# bristol_longshot.net
KiCad netlist of a schematic drawn in EAGLE
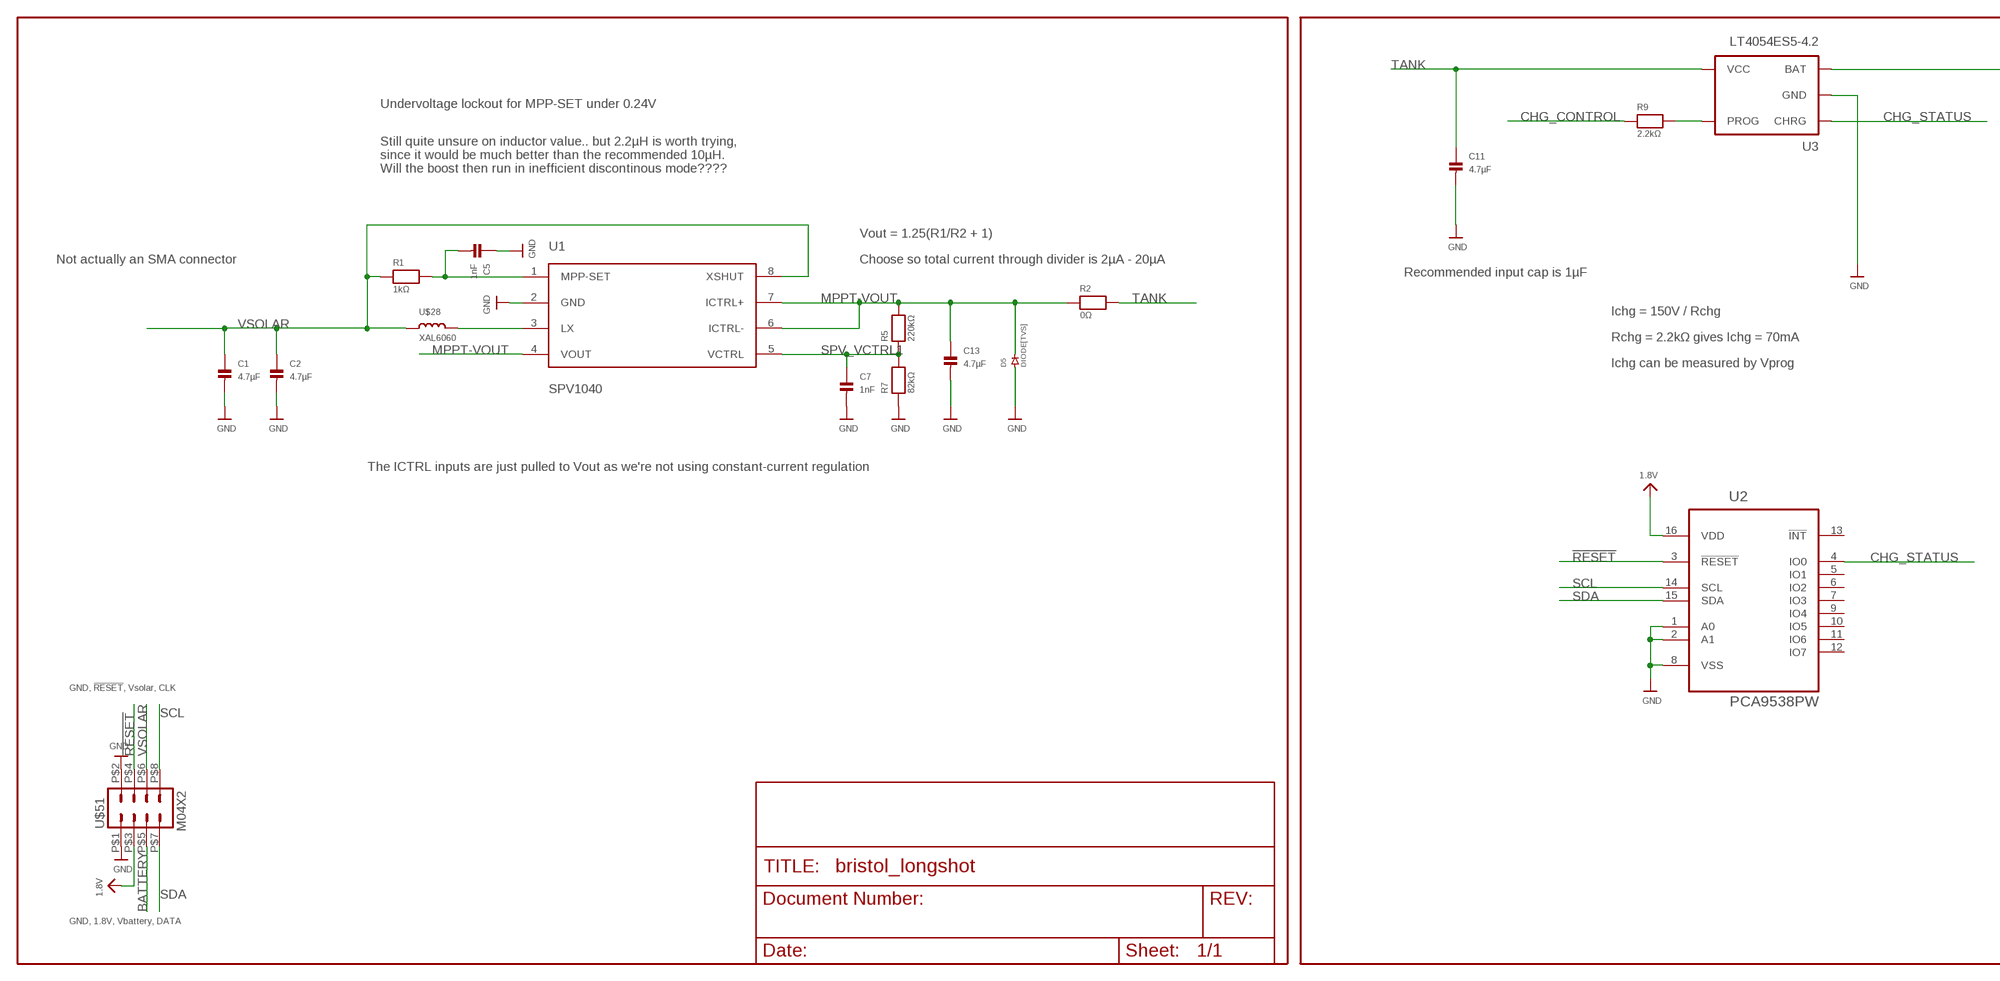
[diagram p0: schematic, sheet 1, part 1 of 2]
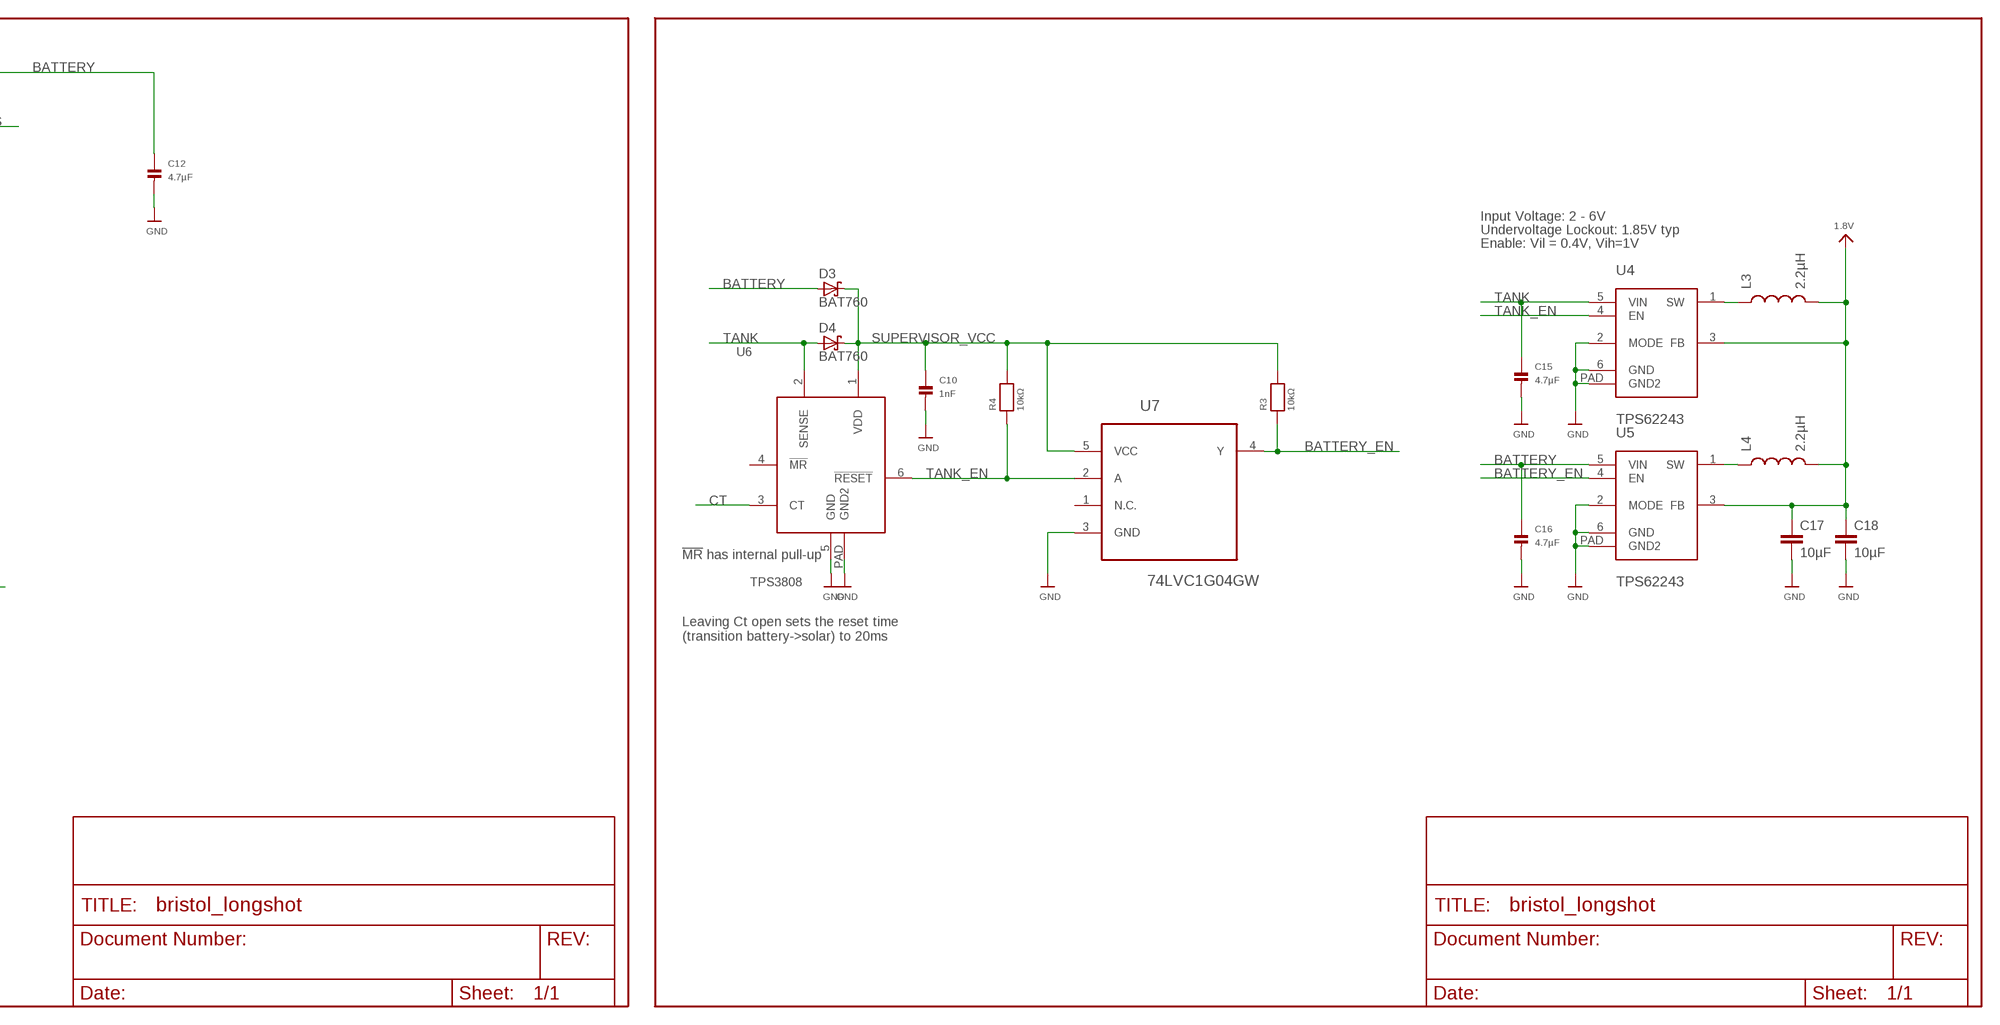
[diagram p1: schematic, sheet 1, part 2 of 2]

(export (version "E")
  (design (tool "Eeschema 10.0.6"))
  (components
    (comp (ref "C1")
      (value "4.7µF")
      (footprint "eagle-import:_0402")
      (libsource (lib "eagle-import") (part "CAP_CERAMIC_0402"))
    )
    (comp (ref "C2")
      (value "4.7µF")
      (footprint "eagle-import:_0402")
      (libsource (lib "eagle-import") (part "CAP_CERAMIC_0402"))
    )
    (comp (ref "C5")
      (value "1nF")
      (footprint "eagle-import:_0402")
      (libsource (lib "eagle-import") (part "CAP_CERAMIC_0402"))
    )
    (comp (ref "C7")
      (value "1nF")
      (footprint "eagle-import:_0402")
      (libsource (lib "eagle-import") (part "CAP_CERAMIC_0402"))
    )
    (comp (ref "C10")
      (value "1nF")
      (footprint "eagle-import:_0402")
      (libsource (lib "eagle-import") (part "CAP_CERAMIC_0402"))
    )
    (comp (ref "C11")
      (value "4.7µF")
      (footprint "eagle-import:_0402")
      (libsource (lib "eagle-import") (part "CAP_CERAMIC_0402"))
    )
    (comp (ref "C12")
      (value "4.7µF")
      (footprint "eagle-import:_0402")
      (libsource (lib "eagle-import") (part "CAP_CERAMIC_0402"))
    )
    (comp (ref "C13")
      (value "4.7µF")
      (footprint "eagle-import:_0402")
      (libsource (lib "eagle-import") (part "CAP_CERAMIC_0402"))
    )
    (comp (ref "C15")
      (value "4.7µF")
      (footprint "eagle-import:_0402")
      (libsource (lib "eagle-import") (part "CAP_CERAMIC_0402"))
    )
    (comp (ref "C16")
      (value "4.7µF")
      (footprint "eagle-import:_0402")
      (libsource (lib "eagle-import") (part "CAP_CERAMIC_0402"))
    )
    (comp (ref "C17")
      (value "10µF")
      (footprint "eagle-import:C0603K")
      (libsource (lib "eagle-import") (part "C-EUC0603K"))
    )
    (comp (ref "C18")
      (value "10µF")
      (footprint "eagle-import:C0603K")
      (libsource (lib "eagle-import") (part "C-EUC0603K"))
    )
    (comp (ref "D3")
      (value "BAT760")
      (footprint "eagle-import:SOD323")
      (libsource (lib "eagle-import") (part "BAT760"))
    )
    (comp (ref "D4")
      (value "BAT760")
      (footprint "eagle-import:SOD323")
      (libsource (lib "eagle-import") (part "BAT760"))
    )
    (comp (ref "D5")
      (value "DIODE[TVS]")
      (footprint "eagle-import:SOD123W")
      (libsource (lib "eagle-import") (part "DIODE[TVS]"))
    )
    (comp (ref "L3")
      (value "2.2µH")
      (footprint "eagle-import:1007")
      (libsource (lib "eagle-import") (part "INDUCTOR1007"))
    )
    (comp (ref "L4")
      (value "2.2µH")
      (footprint "eagle-import:1007")
      (libsource (lib "eagle-import") (part "INDUCTOR1007"))
    )
    (comp (ref "R1")
      (value "1kΩ")
      (footprint "eagle-import:_0402")
      (libsource (lib "eagle-import") (part "RESISTOR_0402"))
    )
    (comp (ref "R2")
      (value "0Ω")
      (footprint "eagle-import:_0402")
      (libsource (lib "eagle-import") (part "RESISTOR_0402"))
    )
    (comp (ref "R3")
      (value "10kΩ")
      (footprint "eagle-import:_0402")
      (libsource (lib "eagle-import") (part "RESISTOR_0402"))
    )
    (comp (ref "R4")
      (value "10kΩ")
      (footprint "eagle-import:_0402")
      (libsource (lib "eagle-import") (part "RESISTOR_0402"))
    )
    (comp (ref "R5")
      (value "220kΩ")
      (footprint "eagle-import:_0402")
      (libsource (lib "eagle-import") (part "RESISTOR_0402"))
    )
    (comp (ref "R7")
      (value "82kΩ")
      (footprint "eagle-import:_0402")
      (libsource (lib "eagle-import") (part "RESISTOR_0402"))
    )
    (comp (ref "R9")
      (value "2.2kΩ")
      (footprint "eagle-import:_0402")
      (libsource (lib "eagle-import") (part "RESISTOR_0402"))
    )
    (comp (ref "U$28")
      (value "XAL6060")
      (footprint "eagle-import:XAL60")
      (libsource (lib "eagle-import") (part "XAL6060"))
    )
    (comp (ref "U$51")
      (value "M04X2")
      (footprint "eagle-import:M04X2")
      (libsource (lib "eagle-import") (part "M04X2"))
    )
    (comp (ref "U1")
      (value "SPV1040")
      (footprint "eagle-import:TSSOP8")
      (libsource (lib "eagle-import") (part "SPV1040"))
    )
    (comp (ref "U2")
      (value "PCA9538PW")
      (footprint "eagle-import:SOP65P640X110-16N")
      (libsource (lib "eagle-import") (part "PCA9538PW"))
    )
    (comp (ref "U3")
      (value "LT4054ES5-4.2")
      (footprint "eagle-import:SOT23-5")
      (libsource (lib "eagle-import") (part "LT4054ES5-4.2"))
    )
    (comp (ref "U4")
      (value "TPS62243")
      (footprint "eagle-import:S-PWSON-N6")
      (libsource (lib "eagle-import") (part "TPS62243"))
    )
    (comp (ref "U5")
      (value "TPS62243")
      (footprint "eagle-import:S-PWSON-N6")
      (libsource (lib "eagle-import") (part "TPS62243"))
    )
    (comp (ref "U6")
      (value "TPS3808")
      (footprint "eagle-import:S-PWSON-N6")
      (libsource (lib "eagle-import") (part "TPS3808"))
    )
    (comp (ref "U7")
      (value "74LVC1G04GW")
      (footprint "eagle-import:SOT65P210X110-5N")
      (libsource (lib "eagle-import") (part "74LVC1G04GW"))
    )
  )
  (nets
    (net (code "1") (name "/BATTERY") (class "Default")
      (node (ref "C12") (pin "1") (pinfunction "P$1_1") (pintype "passive"))
      (node (ref "C16") (pin "1") (pinfunction "P$1_1") (pintype "passive"))
      (node (ref "D3") (pin "A") (pinfunction "A_A") (pintype "passive"))
      (node (ref "U$51") (pin "P$5") (pinfunction "5_P$5") (pintype "passive"))
      (node (ref "U3") (pin "3") (pinfunction "BAT_3") (pintype "input"))
      (node (ref "U5") (pin "5") (pinfunction "VIN_5") (pintype "bidirectional"))
    )
    (net (code "2") (name "/BATTERY_EN") (class "Default")
      (node (ref "R3") (pin "1") (pinfunction "1_1") (pintype "passive"))
      (node (ref "U5") (pin "4") (pinfunction "EN_4") (pintype "bidirectional"))
      (node (ref "U7") (pin "4") (pinfunction "Y_4") (pintype "output"))
    )
    (net (code "3") (name "/CHG_CONTROL") (class "Default")
      (node (ref "R9") (pin "1") (pinfunction "1_1") (pintype "passive"))
    )
    (net (code "4") (name "/CHG_STATUS") (class "Default")
      (node (ref "U2") (pin "4") (pinfunction "IO0_4") (pintype "bidirectional"))
      (node (ref "U3") (pin "1") (pinfunction "CHRG_1") (pintype "input"))
    )
    (net (code "5") (name "/CT") (class "Default")
      (node (ref "U6") (pin "3") (pinfunction "CT_3") (pintype "bidirectional"))
    )
    (net (code "6") (name "/MPPT-VOUT") (class "Default")
      (node (ref "C13") (pin "1") (pinfunction "P$1_1") (pintype "passive"))
      (node (ref "D5") (pin "P$2") (pinfunction "2_P$2") (pintype "bidirectional"))
      (node (ref "R2") (pin "1") (pinfunction "1_1") (pintype "passive"))
      (node (ref "R5") (pin "2") (pinfunction "2_2") (pintype "passive"))
      (node (ref "U1") (pin "4") (pinfunction "VOUT_4") (pintype "bidirectional"))
      (node (ref "U1") (pin "6") (pinfunction "ICTRL-_6") (pintype "bidirectional"))
      (node (ref "U1") (pin "7") (pinfunction "ICTRL+_7") (pintype "bidirectional"))
    )
    (net (code "7") (name "/SCL") (class "Default")
      (node (ref "U$51") (pin "P$8") (pinfunction "8_P$8") (pintype "passive"))
      (node (ref "U2") (pin "14") (pinfunction "SCL_14") (pintype "input"))
    )
    (net (code "8") (name "/SDA") (class "Default")
      (node (ref "U$51") (pin "P$7") (pinfunction "7_P$7") (pintype "passive"))
      (node (ref "U2") (pin "15") (pinfunction "SDA_15") (pintype "bidirectional"))
    )
    (net (code "9") (name "/SPV_VCTRL1") (class "Default")
      (node (ref "C7") (pin "1") (pinfunction "P$1_1") (pintype "passive"))
      (node (ref "R5") (pin "1") (pinfunction "1_1") (pintype "passive"))
      (node (ref "R7") (pin "2") (pinfunction "2_2") (pintype "passive"))
      (node (ref "U1") (pin "5") (pinfunction "VCTRL_5") (pintype "bidirectional"))
    )
    (net (code "10") (name "/SUPERVISOR_VCC") (class "Default")
      (node (ref "C10") (pin "1") (pinfunction "P$1_1") (pintype "passive"))
      (node (ref "D3") (pin "C") (pinfunction "C_C") (pintype "passive"))
      (node (ref "D4") (pin "C") (pinfunction "C_C") (pintype "passive"))
      (node (ref "R3") (pin "2") (pinfunction "2_2") (pintype "passive"))
      (node (ref "R4") (pin "2") (pinfunction "2_2") (pintype "passive"))
      (node (ref "U6") (pin "1") (pinfunction "VDD_1") (pintype "bidirectional"))
      (node (ref "U7") (pin "5") (pinfunction "VCC_5") (pintype "power_in"))
    )
    (net (code "11") (name "/TANK") (class "Default")
      (node (ref "C11") (pin "1") (pinfunction "P$1_1") (pintype "passive"))
      (node (ref "C15") (pin "1") (pinfunction "P$1_1") (pintype "passive"))
      (node (ref "D4") (pin "A") (pinfunction "A_A") (pintype "passive"))
      (node (ref "R2") (pin "2") (pinfunction "2_2") (pintype "passive"))
      (node (ref "U3") (pin "4") (pinfunction "VCC_4") (pintype "input"))
      (node (ref "U4") (pin "5") (pinfunction "VIN_5") (pintype "bidirectional"))
      (node (ref "U6") (pin "2") (pinfunction "SENSE_2") (pintype "bidirectional"))
    )
    (net (code "12") (name "/TANK_EN") (class "Default")
      (node (ref "R4") (pin "1") (pinfunction "1_1") (pintype "passive"))
      (node (ref "U4") (pin "4") (pinfunction "EN_4") (pintype "bidirectional"))
      (node (ref "U6") (pin "6") (pinfunction "~{RESET}_6") (pintype "bidirectional"))
      (node (ref "U7") (pin "2") (pinfunction "A_2") (pintype "input"))
    )
    (net (code "13") (name "/VSOLAR") (class "Default")
      (node (ref "C1") (pin "1") (pinfunction "P$1_1") (pintype "passive"))
      (node (ref "C2") (pin "1") (pinfunction "P$1_1") (pintype "passive"))
      (node (ref "R1") (pin "1") (pinfunction "1_1") (pintype "passive"))
      (node (ref "U$28") (pin "P$1") (pinfunction "1_P$1") (pintype "passive"))
      (node (ref "U$51") (pin "P$6") (pinfunction "6_P$6") (pintype "passive"))
      (node (ref "U1") (pin "8") (pinfunction "XSHUT_8") (pintype "bidirectional"))
    )
    (net (code "14") (name "/~{RESET}") (class "Default")
      (node (ref "U$51") (pin "P$4") (pinfunction "4_P$4") (pintype "passive"))
      (node (ref "U2") (pin "3") (pinfunction "~{RESET}_3") (pintype "input"))
    )
    (net (code "15") (name "1.8V") (class "Default")
      (node (ref "C17") (pin "1") (pinfunction "1_1") (pintype "passive"))
      (node (ref "C18") (pin "1") (pinfunction "1_1") (pintype "passive"))
      (node (ref "L3") (pin "2") (pinfunction "2_2") (pintype "passive"))
      (node (ref "L4") (pin "2") (pinfunction "2_2") (pintype "passive"))
      (node (ref "U$51") (pin "P$3") (pinfunction "3_P$3") (pintype "passive"))
      (node (ref "U2") (pin "16") (pinfunction "VDD_16") (pintype "power_in"))
      (node (ref "U4") (pin "3") (pinfunction "FB_3") (pintype "bidirectional"))
      (node (ref "U5") (pin "3") (pinfunction "FB_3") (pintype "bidirectional"))
    )
    (net (code "16") (name "GND") (class "Default")
      (node (ref "C1") (pin "2") (pinfunction "P$2_2") (pintype "passive"))
      (node (ref "C10") (pin "2") (pinfunction "P$2_2") (pintype "passive"))
      (node (ref "C11") (pin "2") (pinfunction "P$2_2") (pintype "passive"))
      (node (ref "C12") (pin "2") (pinfunction "P$2_2") (pintype "passive"))
      (node (ref "C13") (pin "2") (pinfunction "P$2_2") (pintype "passive"))
      (node (ref "C15") (pin "2") (pinfunction "P$2_2") (pintype "passive"))
      (node (ref "C16") (pin "2") (pinfunction "P$2_2") (pintype "passive"))
      (node (ref "C17") (pin "2") (pinfunction "2_2") (pintype "passive"))
      (node (ref "C18") (pin "2") (pinfunction "2_2") (pintype "passive"))
      (node (ref "C2") (pin "2") (pinfunction "P$2_2") (pintype "passive"))
      (node (ref "C5") (pin "1") (pinfunction "P$1_1") (pintype "passive"))
      (node (ref "C7") (pin "2") (pinfunction "P$2_2") (pintype "passive"))
      (node (ref "D5") (pin "P$1") (pinfunction "1_P$1") (pintype "bidirectional"))
      (node (ref "R7") (pin "1") (pinfunction "1_1") (pintype "passive"))
      (node (ref "U$51") (pin "P$1") (pinfunction "1_P$1") (pintype "passive"))
      (node (ref "U$51") (pin "P$2") (pinfunction "2_P$2") (pintype "passive"))
      (node (ref "U1") (pin "2") (pinfunction "GND_2") (pintype "power_in"))
      (node (ref "U2") (pin "1") (pinfunction "A0_1") (pintype "input"))
      (node (ref "U2") (pin "2") (pinfunction "A1_2") (pintype "input"))
      (node (ref "U2") (pin "8") (pinfunction "VSS_8") (pintype "passive"))
      (node (ref "U3") (pin "2") (pinfunction "GND_2") (pintype "input"))
      (node (ref "U4") (pin "2") (pinfunction "MODE_2") (pintype "bidirectional"))
      (node (ref "U4") (pin "6") (pinfunction "GND_6") (pintype "bidirectional"))
      (node (ref "U4") (pin "PAD") (pinfunction "GND2_PAD") (pintype "bidirectional"))
      (node (ref "U5") (pin "2") (pinfunction "MODE_2") (pintype "bidirectional"))
      (node (ref "U5") (pin "6") (pinfunction "GND_6") (pintype "bidirectional"))
      (node (ref "U5") (pin "PAD") (pinfunction "GND2_PAD") (pintype "bidirectional"))
      (node (ref "U6") (pin "5") (pinfunction "GND_5") (pintype "bidirectional"))
      (node (ref "U6") (pin "PAD") (pinfunction "GND2_PAD") (pintype "bidirectional"))
      (node (ref "U7") (pin "3") (pinfunction "GND_3") (pintype "passive"))
    )
    (net (code "17") (name "Net-(C5-P$2)") (class "Default")
      (node (ref "C5") (pin "2") (pinfunction "P$2_2") (pintype "passive"))
      (node (ref "R1") (pin "2") (pinfunction "2_2") (pintype "passive"))
      (node (ref "U1") (pin "1") (pinfunction "MPP-SET_1") (pintype "bidirectional"))
    )
    (net (code "18") (name "Net-(U$28-2)") (class "Default")
      (node (ref "U$28") (pin "P$2") (pinfunction "2_P$2") (pintype "passive"))
      (node (ref "U1") (pin "3") (pinfunction "LX_3") (pintype "bidirectional"))
    )
    (net (code "19") (name "Net-(U3-PROG)") (class "Default")
      (node (ref "R9") (pin "2") (pinfunction "2_2") (pintype "passive"))
      (node (ref "U3") (pin "5") (pinfunction "PROG_5") (pintype "passive"))
    )
    (net (code "20") (name "Net-(U4-SW)") (class "Default")
      (node (ref "L3") (pin "1") (pinfunction "1_1") (pintype "passive"))
      (node (ref "U4") (pin "1") (pinfunction "SW_1") (pintype "bidirectional"))
    )
    (net (code "21") (name "Net-(U5-SW)") (class "Default")
      (node (ref "L4") (pin "1") (pinfunction "1_1") (pintype "passive"))
      (node (ref "U5") (pin "1") (pinfunction "SW_1") (pintype "bidirectional"))
    )
    (net (code "22") (name "unconnected-(U2-IO1-Pad5)") (class "Default")
      (node (ref "U2") (pin "5") (pinfunction "IO1_5") (pintype "bidirectional"))
    )
    (net (code "23") (name "unconnected-(U2-IO2-Pad6)") (class "Default")
      (node (ref "U2") (pin "6") (pinfunction "IO2_6") (pintype "bidirectional"))
    )
    (net (code "24") (name "unconnected-(U2-IO3-Pad7)") (class "Default")
      (node (ref "U2") (pin "7") (pinfunction "IO3_7") (pintype "bidirectional"))
    )
    (net (code "25") (name "unconnected-(U2-IO4-Pad9)") (class "Default")
      (node (ref "U2") (pin "9") (pinfunction "IO4_9") (pintype "bidirectional"))
    )
    (net (code "26") (name "unconnected-(U2-IO5-Pad10)") (class "Default")
      (node (ref "U2") (pin "10") (pinfunction "IO5_10") (pintype "bidirectional"))
    )
    (net (code "27") (name "unconnected-(U2-IO6-Pad11)") (class "Default")
      (node (ref "U2") (pin "11") (pinfunction "IO6_11") (pintype "bidirectional"))
    )
    (net (code "28") (name "unconnected-(U2-IO7-Pad12)") (class "Default")
      (node (ref "U2") (pin "12") (pinfunction "IO7_12") (pintype "bidirectional"))
    )
    (net (code "29") (name "unconnected-(U2-~{INT}-Pad13)") (class "Default")
      (node (ref "U2") (pin "13") (pinfunction "~{INT}_13") (pintype "bidirectional"))
    )
    (net (code "30") (name "unconnected-(U6-~{MR}-Pad4)") (class "Default")
      (node (ref "U6") (pin "4") (pinfunction "~{MR}_4") (pintype "bidirectional"))
    )
    (net (code "31") (name "unconnected-(U7-N.C.-Pad1)") (class "Default")
      (node (ref "U7") (pin "1") (pinfunction "N.C._1") (pintype "no_connect"))
    )
  )
)
